# Optoisolator-v12.net
KiCad netlist of a schematic drawn in EAGLE
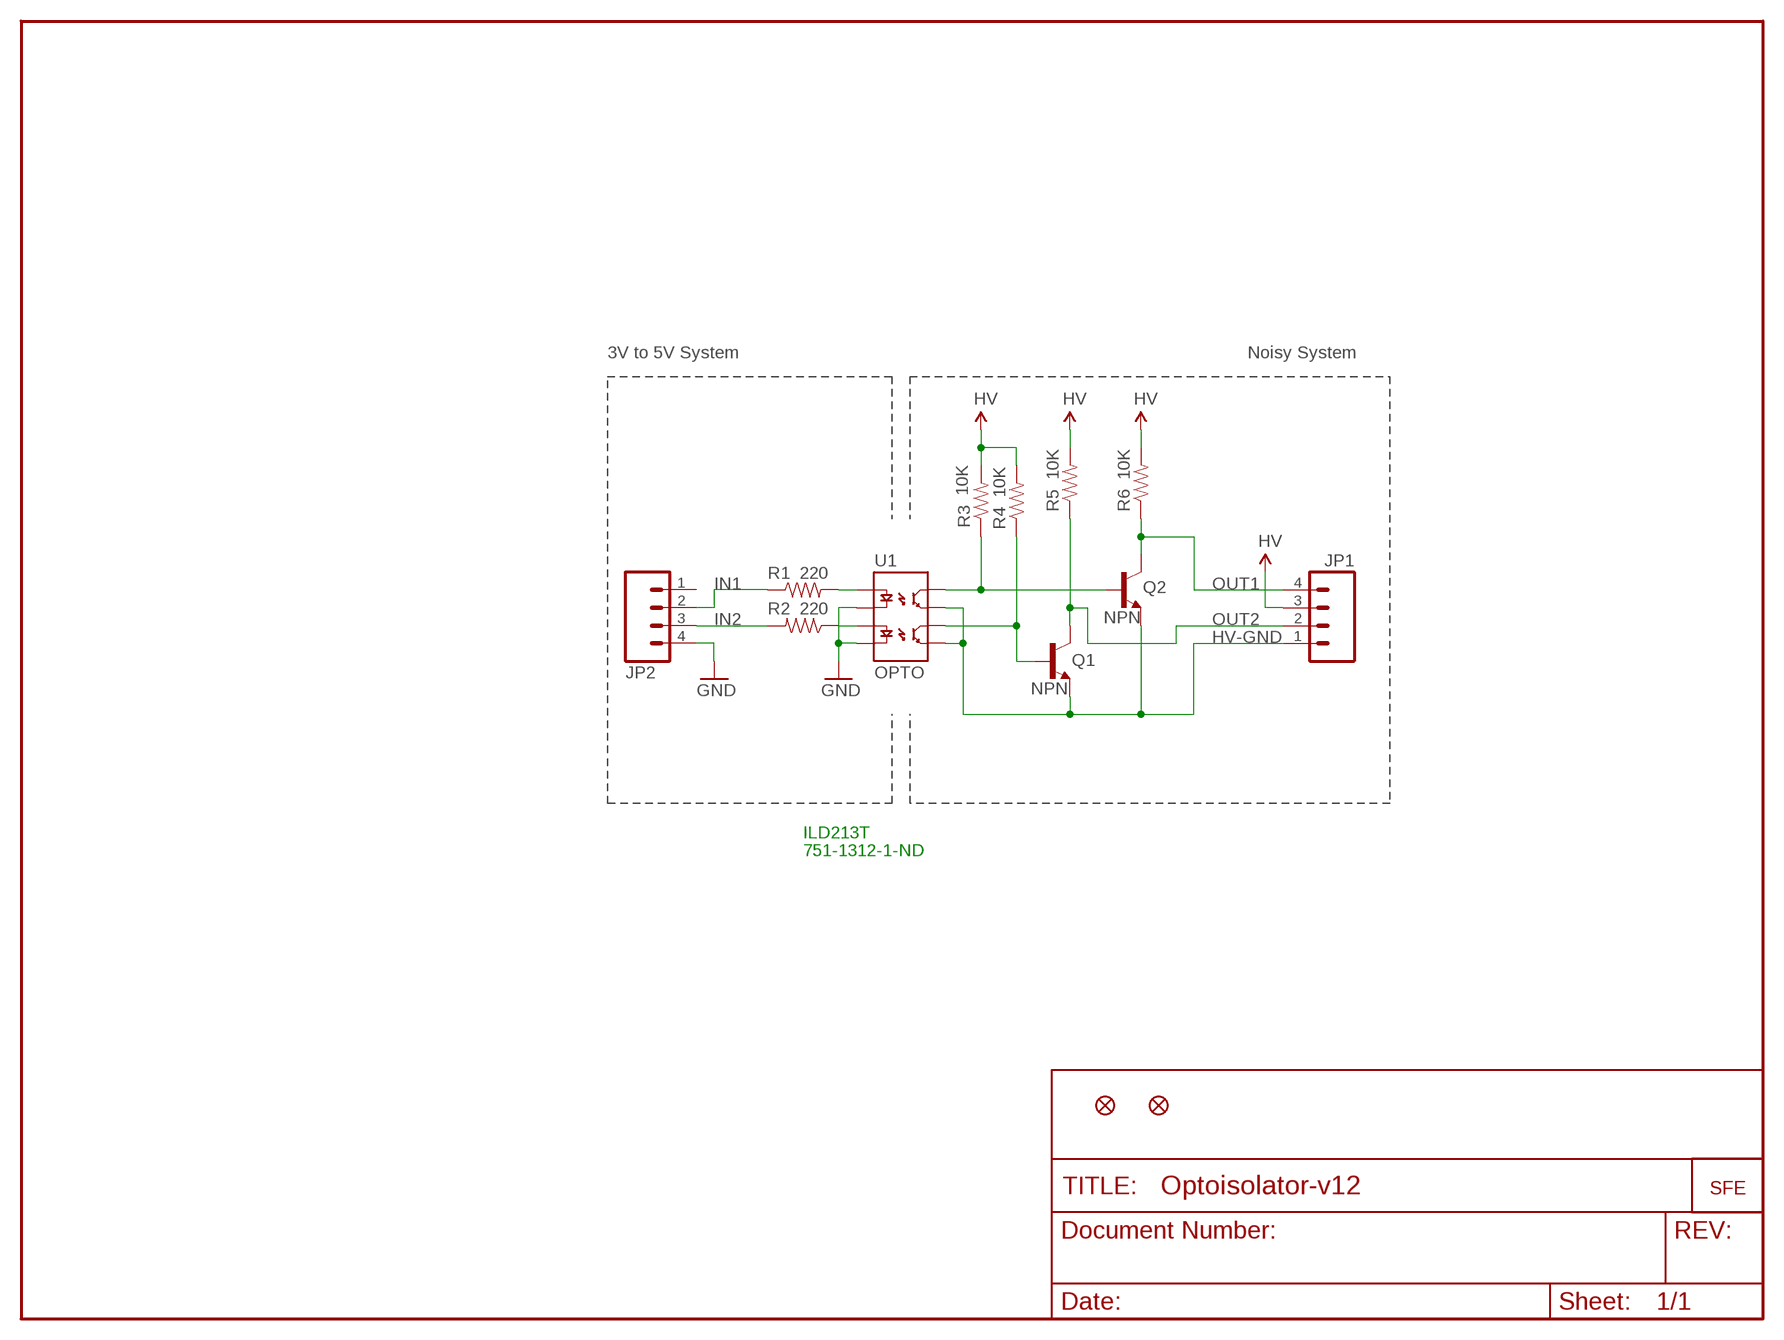
[diagram p0: schematic, sheet 1]

(export (version "E")
  (design (tool "Eeschema 10.0.6"))
  (components
    (comp (ref "JP1")
      (value "M04PTH")
      (footprint "eagle-import:1X04")
      (libsource (lib "eagle-import") (part "M04PTH"))
    )
    (comp (ref "JP2")
      (value "M04PTH")
      (footprint "eagle-import:1X04")
      (libsource (lib "eagle-import") (part "M04PTH"))
    )
    (comp (ref "Q1")
      (value "NPN")
      (footprint "eagle-import:SOT23-3")
      (libsource (lib "eagle-import") (part "TRANSISTOR_NPNSOT23-3"))
    )
    (comp (ref "Q2")
      (value "NPN")
      (footprint "eagle-import:SOT23-3")
      (libsource (lib "eagle-import") (part "TRANSISTOR_NPNSOT23-3"))
    )
    (comp (ref "R1")
      (value "220")
      (footprint "eagle-import:C0402")
      (libsource (lib "eagle-import") (part "RESISTOR0402"))
    )
    (comp (ref "R2")
      (value "220")
      (footprint "eagle-import:C0402")
      (libsource (lib "eagle-import") (part "RESISTOR0402"))
    )
    (comp (ref "R3")
      (value "10K")
      (footprint "eagle-import:C0402")
      (libsource (lib "eagle-import") (part "RESISTOR0402"))
    )
    (comp (ref "R4")
      (value "10K")
      (footprint "eagle-import:C0402")
      (libsource (lib "eagle-import") (part "RESISTOR0402"))
    )
    (comp (ref "R5")
      (value "10K")
      (footprint "eagle-import:C0402")
      (libsource (lib "eagle-import") (part "RESISTOR0402"))
    )
    (comp (ref "R6")
      (value "10K")
      (footprint "eagle-import:C0402")
      (libsource (lib "eagle-import") (part "RESISTOR0402"))
    )
    (comp (ref "U$1")
      (value "LOGO-SFESK")
      (footprint "eagle-import:SFE-LOGO-FLAME")
      (libsource (lib "eagle-import") (part "LOGO-SFESK"))
    )
    (comp (ref "U$2")
      (value "FIDUCIAL1X2")
      (footprint "eagle-import:FIDUCIAL-1X2")
      (libsource (lib "eagle-import") (part "FIDUCIAL1X2"))
    )
    (comp (ref "U$3")
      (value "FIDUCIAL1X2")
      (footprint "eagle-import:FIDUCIAL-1X2")
      (libsource (lib "eagle-import") (part "FIDUCIAL1X2"))
    )
    (comp (ref "U1")
      (value "OPTO")
      (footprint "eagle-import:SO08-2")
      (libsource (lib "eagle-import") (part "OPTOISOLATOR-2SOIC8"))
    )
  )
  (nets
    (net (code "1") (name "/HV-GND") (class "Default")
      (node (ref "JP1") (pin "1") (pinfunction "1_1") (pintype "passive"))
      (node (ref "Q1") (pin "2") (pinfunction "E_2") (pintype "passive"))
      (node (ref "Q2") (pin "2") (pinfunction "E_2") (pintype "passive"))
      (node (ref "U1") (pin "5") (pinfunction "EM2_5") (pintype "bidirectional"))
      (node (ref "U1") (pin "7") (pinfunction "EM1_7") (pintype "bidirectional"))
    )
    (net (code "2") (name "/IN1") (class "Default")
      (node (ref "JP2") (pin "2") (pinfunction "2_2") (pintype "passive"))
      (node (ref "R1") (pin "1") (pinfunction "1_1") (pintype "passive"))
    )
    (net (code "3") (name "/IN2") (class "Default")
      (node (ref "JP2") (pin "3") (pinfunction "3_3") (pintype "passive"))
      (node (ref "R2") (pin "2") (pinfunction "2_2") (pintype "passive"))
    )
    (net (code "4") (name "/OUT1") (class "Default")
      (node (ref "JP1") (pin "4") (pinfunction "4_4") (pintype "passive"))
      (node (ref "Q2") (pin "3") (pinfunction "C_3") (pintype "passive"))
      (node (ref "R6") (pin "1") (pinfunction "1_1") (pintype "passive"))
    )
    (net (code "5") (name "/OUT2") (class "Default")
      (node (ref "JP1") (pin "2") (pinfunction "2_2") (pintype "passive"))
      (node (ref "Q1") (pin "3") (pinfunction "C_3") (pintype "passive"))
      (node (ref "R5") (pin "1") (pinfunction "1_1") (pintype "passive"))
    )
    (net (code "6") (name "GND") (class "Default")
      (node (ref "JP2") (pin "4") (pinfunction "4_4") (pintype "passive"))
      (node (ref "U1") (pin "2") (pinfunction "C1_2") (pintype "bidirectional"))
      (node (ref "U1") (pin "4") (pinfunction "C2_4") (pintype "bidirectional"))
    )
    (net (code "7") (name "HV") (class "Default")
      (node (ref "JP1") (pin "3") (pinfunction "3_3") (pintype "passive"))
      (node (ref "R3") (pin "2") (pinfunction "2_2") (pintype "passive"))
      (node (ref "R4") (pin "2") (pinfunction "2_2") (pintype "passive"))
      (node (ref "R5") (pin "2") (pinfunction "2_2") (pintype "passive"))
      (node (ref "R6") (pin "2") (pinfunction "2_2") (pintype "passive"))
    )
    (net (code "8") (name "Net-(Q1-B)") (class "Default")
      (node (ref "Q1") (pin "1") (pinfunction "B_1") (pintype "passive"))
      (node (ref "R4") (pin "1") (pinfunction "1_1") (pintype "passive"))
      (node (ref "U1") (pin "6") (pinfunction "CL2_6") (pintype "bidirectional"))
    )
    (net (code "9") (name "Net-(Q2-B)") (class "Default")
      (node (ref "Q2") (pin "1") (pinfunction "B_1") (pintype "passive"))
      (node (ref "R3") (pin "1") (pinfunction "1_1") (pintype "passive"))
      (node (ref "U1") (pin "8") (pinfunction "CL1_8") (pintype "bidirectional"))
    )
    (net (code "10") (name "Net-(U1-A1)") (class "Default")
      (node (ref "R1") (pin "2") (pinfunction "2_2") (pintype "passive"))
      (node (ref "U1") (pin "1") (pinfunction "A1_1") (pintype "bidirectional"))
    )
    (net (code "11") (name "Net-(U1-A2)") (class "Default")
      (node (ref "R2") (pin "1") (pinfunction "1_1") (pintype "passive"))
      (node (ref "U1") (pin "3") (pinfunction "A2_3") (pintype "bidirectional"))
    )
    (net (code "12") (name "unconnected-(JP2-Pad1)") (class "Default")
      (node (ref "JP2") (pin "1") (pinfunction "1_1") (pintype "passive"))
    )
  )
)
